# INMP441MEMSMicrophone_v04x.net
KiCad netlist of a schematic drawn in EAGLE
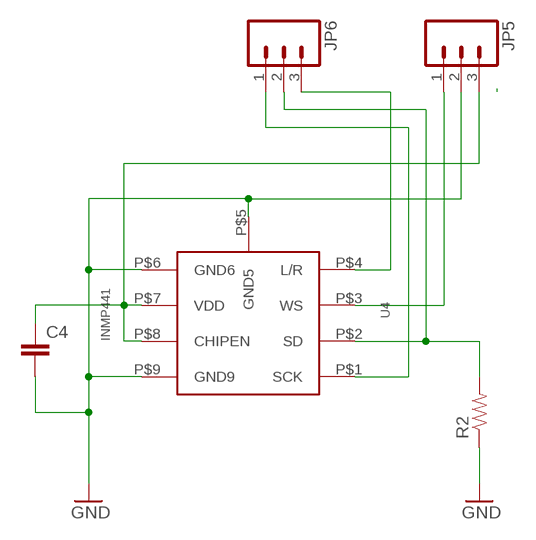
[diagram p0: schematic, sheet 1]

(export (version "E")
  (design (tool "Eeschema 10.0.6"))
  (components
    (comp (ref "C4")
      (value "CAP0402-CAP")
      (footprint "eagle-import:0402-CAP")
      (libsource (lib "eagle-import") (part "CAP0402-CAP"))
    )
    (comp (ref "JP5")
      (value "M031X03_NO_SILK")
      (footprint "eagle-import:1X03_NO_SILK")
      (libsource (lib "eagle-import") (part "M031X03_NO_SILK"))
    )
    (comp (ref "JP6")
      (value "M031X03_NO_SILK")
      (footprint "eagle-import:1X03_NO_SILK")
      (libsource (lib "eagle-import") (part "M031X03_NO_SILK"))
    )
    (comp (ref "R2")
      (value "RESISTOR0402-RES")
      (footprint "eagle-import:0402-RES")
      (libsource (lib "eagle-import") (part "RESISTOR0402-RES"))
    )
    (comp (ref "U4")
      (value "INMP441")
      (footprint "eagle-import:INMP441")
      (libsource (lib "eagle-import") (part "INMP441"))
    )
  )
  (nets
    (net (code "1") (name "GND") (class "Default")
      (node (ref "C4") (pin "2") (pinfunction "2_2") (pintype "passive"))
      (node (ref "JP5") (pin "2") (pinfunction "2_2") (pintype "passive"))
      (node (ref "R2") (pin "1") (pinfunction "1_1") (pintype "passive"))
      (node (ref "U4") (pin "P$5") (pinfunction "GND5_P$5") (pintype "power_in"))
      (node (ref "U4") (pin "P$6") (pinfunction "GND6_P$6") (pintype "power_in"))
      (node (ref "U4") (pin "P$9") (pinfunction "GND9_P$9") (pintype "power_in"))
    )
    (net (code "2") (name "Net-(U4-CHIPEN)") (class "Default")
      (node (ref "C4") (pin "1") (pinfunction "1_1") (pintype "passive"))
      (node (ref "JP5") (pin "3") (pinfunction "3_3") (pintype "passive"))
      (node (ref "U4") (pin "P$7") (pinfunction "VDD_P$7") (pintype "power_in"))
      (node (ref "U4") (pin "P$8") (pinfunction "CHIPEN_P$8") (pintype "input"))
    )
    (net (code "3") (name "Net-(U4-L{slash}R)") (class "Default")
      (node (ref "JP6") (pin "3") (pinfunction "3_3") (pintype "passive"))
      (node (ref "U4") (pin "P$4") (pinfunction "L/R_P$4") (pintype "input"))
    )
    (net (code "4") (name "Net-(U4-SCK)") (class "Default")
      (node (ref "JP6") (pin "1") (pinfunction "1_1") (pintype "passive"))
      (node (ref "U4") (pin "P$1") (pinfunction "SCK_P$1") (pintype "input"))
    )
    (net (code "5") (name "Net-(U4-SD)") (class "Default")
      (node (ref "JP6") (pin "2") (pinfunction "2_2") (pintype "passive"))
      (node (ref "R2") (pin "2") (pinfunction "2_2") (pintype "passive"))
      (node (ref "U4") (pin "P$2") (pinfunction "SD_P$2") (pintype "bidirectional"))
    )
    (net (code "6") (name "Net-(U4-WS)") (class "Default")
      (node (ref "JP5") (pin "1") (pinfunction "1_1") (pintype "passive"))
      (node (ref "U4") (pin "P$3") (pinfunction "WS_P$3") (pintype "input"))
    )
  )
)
